# ActuatorMKII_Circuits.net
KiCad netlist of a schematic drawn in Altium Designer
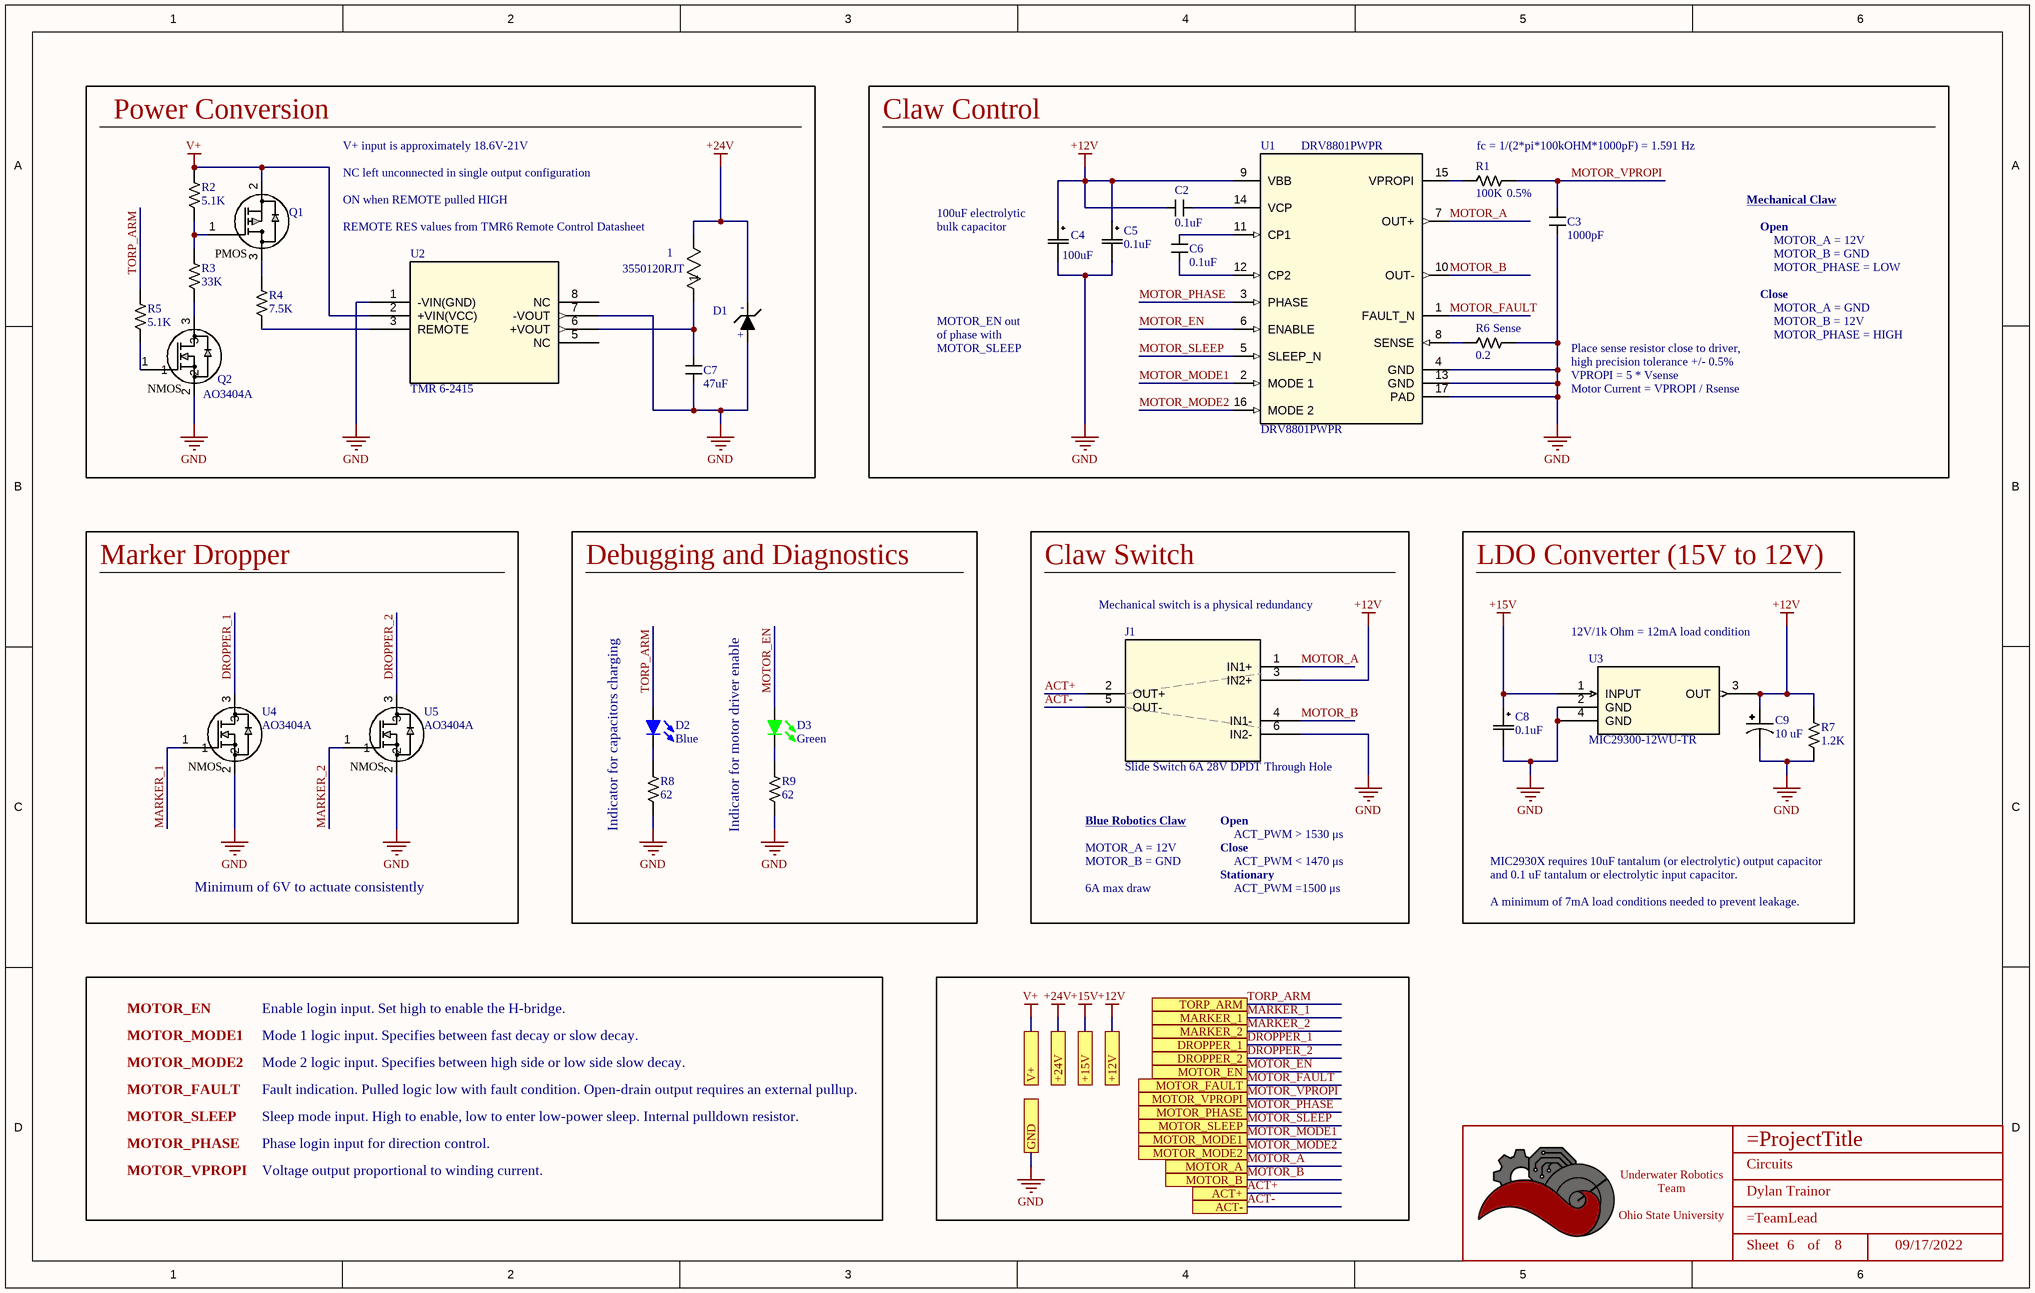
[diagram p0: ActuatorMKII_Circuits.SchDoc]

(export (version "E")
  (design (tool "Eeschema 10.0.6"))
  (components
    (comp (ref "*")
      (value "Title_Block")
      (footprint "LOGO")
      (description "UWRT Schematic Title Block Template\r\n\r\nCreated June 2021, Dylan Trainor")
      (libsource (lib "UWRT") (part "Title_Block"))
    )
    (comp (ref "1")
      (value "3550120RJT")
      (footprint "RES_3550_TEC")
      (description "RES 3550 120R 5%")
      (fields (field (name "COPYRIGHT") "Copyright (C) 2022 Ultra Librarian. All rights reserved."))
      (libsource (lib "Resistors") (part "3550120RJT"))
    )
    (comp (ref "C2")
      (value "0.1uF")
      (footprint "CAPACITOR_0805")
      (description "Cap 100nF 50V +/-10%\r\nCeramic 0805")
      (fields
        (field (name "TOLERANCE") "+/- 10%")
        (field (name "VOLTAGE") "25V")
        (field (name "MADE BY") "Robert Pafford")
      )
      (libsource (lib "Capacitors") (part "CAPACITOR_0.1uF_0402_1"))
    )
    (comp (ref "C3")
      (value "1000pF")
      (footprint "CAPACITOR_0603")
      (description "Cap 1000pF 50V +/-2%\r\nCeramic 0603")
      (fields
        (field (name "TOLERANCE") "+/- 2%")
        (field (name "VOLTAGE") "50")
        (field (name "MADE BY") "Flip B")
      )
      (libsource (lib "Capacitors") (part "CAPACITOR_0.001uF_0603"))
    )
    (comp (ref "C4")
      (value "100uF")
      (footprint "CAPAE830X1100N")
      (description "Aluminum Electrolytic Capacitors - SMD 35V 100uF 0810 20%")
      (fields (field (name "CREATED BY") "John Ulm"))
      (libsource (lib "Capacitors") (part "CAP ALUM 100UF 20% 35V SMD (2)"))
    )
    (comp (ref "C5")
      (value "0.1uF")
      (footprint "U2-D_NCH")
      (description "0.1 µF 35 V Aluminum Electrolytic Capacitors Radial, Can - SMD 7000 Hrs @ 105°C")
      (fields
        (field (name "MANUFACTURER_PART_NUMBER") "UCB1V0R1MCL1GS")
        (field (name "Comment") "0.1uF electrolytic 35 V")
        (field (name "COPYRIGHT") "Copyright (C) 2022 Ultra Librarian. All rights reserved.")
        (field (name "MADE BY") "Tyson Nguyen")
      )
      (libsource (lib "Capacitors") (part "CAP ALUM 0.1UF 20% 35V SMD"))
    )
    (comp (ref "C6")
      (value "0.1uF")
      (footprint "CAPACITOR_0805")
      (description "Cap 100nF 50V +/-10%\r\nCeramic 0805")
      (fields
        (field (name "TOLERANCE") "+/- 10%")
        (field (name "VOLTAGE") "25V")
        (field (name "MADE BY") "Robert Pafford")
      )
      (libsource (lib "Capacitors") (part "CAPACITOR_0.1uF_0402_1"))
    )
    (comp (ref "C7")
      (value "47uF")
      (footprint "PCAP_8x5.4-ELECT_NCA")
      (description "CAP ALUM 47uF 50V +/-20%\r\n8x5.4")
      (fields
        (field (name "TOLERANCE") "+/- 20%")
        (field (name "VOLTAGE") "6.3V")
        (field (name "MADE BY") "Flip B")
      )
      (libsource (lib "Capacitors") (part "CAP_ALUM_47uF"))
    )
    (comp (ref "C8")
      (value "0.1uF")
      (footprint "U2-D_NCH")
      (description "0.1 µF 35 V Aluminum Electrolytic Capacitors Radial, Can - SMD 7000 Hrs @ 105°C")
      (fields
        (field (name "MANUFACTURER_PART_NUMBER") "UCB1V0R1MCL1GS")
        (field (name "Comment") "0.1uF electrolytic 35 V")
        (field (name "COPYRIGHT") "Copyright (C) 2022 Ultra Librarian. All rights reserved.")
        (field (name "MADE BY") "Tyson Nguyen")
      )
      (libsource (lib "Capacitors") (part "CAP ALUM 0.1UF 20% 35V SMD"))
    )
    (comp (ref "C9")
      (value "10uF Tantalum 16V")
      (footprint "CAPACITOR_1206 - POLAR")
      (description "Cap 10uF 16V +/-20%\r\nTantalum 1206")
      (fields
        (field (name "TOLERANCE") "+/- 10%")
        (field (name "VOLTAGE") "16V")
        (field (name "VALUE (UF)") "10 uF")
        (field (name "MADE BY") "Dylan T")
      )
      (libsource (lib "Capacitors") (part "CAPACITOR_10uF_1206_Tantalum_1"))
    )
    (comp (ref "D1")
      (value "Zener_Diode_10V_410mW")
      (footprint "SOD-123")
      (description "Zener Diode ¦ 10 V ¦ 410 mW ¦ SOD 123")
      (fields (field (name "POWER") "410mW") (field (name "MADE BY") "Nathan A"))
      (libsource (lib "Diodes") (part "Zener_Diode_10V_410mW"))
    )
    (comp (ref "D2")
      (value "150060BS75000")
      (footprint "LED_0603")
      (description "LED Blue Vf= 3.2V If = 0.020A\r\n150060BS75000")
      (fields (field (name "COLOR") "Blue") (field (name "MADE BY") "Robert Pafford"))
      (libsource (lib "Diodes") (part "LED_Blue_0603"))
    )
    (comp (ref "D3")
      (value "IN-S63AT5G")
      (footprint "LED_0603")
      (description "LED Green Vf= 3V If = 0.005A\r\nIN-S63AT5G")
      (fields (field (name "COLOR") "Green") (field (name "MADE BY") "Robert Pafford"))
      (libsource (lib "Diodes") (part "LED_Green_0603_3V"))
    )
    (comp (ref "J1")
      (value "Slide Switch 6A 28V DPDT Through Hole")
      (footprint "CONN_S3CQE2")
      (description "SWITCH SLIDE DPDT 6A 28V Through Hole")
      (fields
        (field (name "MANUFACTURER_PART_NUMBER") "1201M2S3CQE2")
        (field (name "COPYRIGHT") "Copyright (C) 2022 Ultra Librarian. All rights reserved.")
      )
      (libsource (lib "Switches") (part "Slide DPDT Switch"))
    )
    (comp (ref "Q1")
      (value "DMP3056L-7")
      (footprint "SOT-23-3")
      (description "P-Channel 30V 4.3A (Ta) 1.38W (Ta) Surface Mount SOT23")
      (fields (field (name "CREATED BY") "John Ulm") (field (name "REVIEWED BY") "---"))
      (libsource (lib "Transistors") (part "DMP3056L-7"))
    )
    (comp (ref "Q2")
      (value "AO3404A")
      (footprint "SOT-23-3")
      (description "N-Channel 30 V 5.8A (Ta) 1.4W (Ta) Surface Mount SOT-23-3")
      (fields (field (name "CREATED BY") "Dylan T"))
      (libsource (lib "Transistors") (part "AO3404A"))
    )
    (comp (ref "R1")
      (value "100k Ohm 5% 1/8W")
      (footprint "RESISTOR_0603")
      (description "RES 100k OHM 5% 1/10W 0603")
      (fields
        (field (name "TOLERANCE") "+/- 5%")
        (field (name "VALUE  (OHMS)") "100K")
        (field (name "MADE BY") "Flip B")
      )
      (libsource (lib "Resistors") (part "RESISTOR_100K_0603_1"))
    )
    (comp (ref "R2")
      (value "5.1k Ohm 1% 1/8W")
      (footprint "RESISTOR_0805")
      (description "RES 5.1k OHM 1% 1/8W 0805")
      (fields
        (field (name "TOLERANCE") "+/- 5%")
        (field (name "VALUE  (OHMS)") "5.1K")
        (field (name "MADE BY") "Dylan Trainor")
      )
      (libsource (lib "Resistors") (part "RESISTOR_5.1K_0805"))
    )
    (comp (ref "R3")
      (value "33k Ohm 5% 1/8W")
      (footprint "RESISTOR_0805")
      (description "RES 33k OHM 5% 1/8W 0805")
      (fields
        (field (name "TOLERANCE") "+/- 5%")
        (field (name "VALUE  (OHMS)") "33K")
        (field (name "MADE BY") "Dylan Trainor")
      )
      (libsource (lib "Resistors") (part "RESISTOR_33K_0805"))
    )
    (comp (ref "R4")
      (value "7.5k Ohm 5% 1/10W")
      (footprint "RESISTOR_0603")
      (description "RES 7.5k OHM 5% 1/10W 0603")
      (fields
        (field (name "TOLERANCE") "+/- 5%")
        (field (name "VALUE  (OHMS)") "7.5K")
        (field (name "MADE BY") "Dylan Trainor")
      )
      (libsource (lib "Resistors") (part "RESISTOR_7.5K_0603"))
    )
    (comp (ref "R5")
      (value "5.1k Ohm 1% 1/8W")
      (footprint "RESISTOR_0805")
      (description "RES 5.1k OHM 1% 1/8W 0805")
      (fields
        (field (name "TOLERANCE") "+/- 5%")
        (field (name "VALUE  (OHMS)") "5.1K")
        (field (name "MADE BY") "Dylan Trainor")
      )
      (libsource (lib "Resistors") (part "RESISTOR_5.1K_0805"))
    )
    (comp (ref "R6")
      (value "0.2 Ohm 1% 2W 2512")
      (footprint "RESISTOR_2512")
      (description "RES 0.2 OHM 1% 2W 2512")
      (fields
        (field (name "TOLERANCE") "+/- 1%")
        (field (name "VALUE  (OHMS)") "0.2")
        (field (name "MADE BY") "Dylan Trainor")
      )
      (libsource (lib "Resistors") (part "RESISTOR_0.2_1%_2512"))
    )
    (comp (ref "R7")
      (value "1.2k Ohm 5% 1/2W")
      (footprint "RESISTOR_0805")
      (description "RES 1.2k OHM 5% 1/2W 0805")
      (fields
        (field (name "TOLERANCE") "+/- 5%")
        (field (name "VALUE  (OHMS)") "1.2K")
        (field (name "MADE BY") "Robert Pafford")
      )
      (libsource (lib "Resistors") (part "RESISTOR_1.2K_0805"))
    )
    (comp (ref "R8")
      (value "62 Ohm 1% 1/4W")
      (footprint "RESISTOR_0603")
      (description "RES SMD 62 OHM 1% 1/4W 0603")
      (fields
        (field (name "TOLERANCE") "+/- 1%")
        (field (name "VALUE  (OHMS)") "62")
        (field (name "MADE BY") "Robert Pafford")
      )
      (libsource (lib "Resistors") (part "RESISTOR_62_0603"))
    )
    (comp (ref "R9")
      (value "62 Ohm 1% 1/4W")
      (footprint "RESISTOR_0603")
      (description "RES SMD 62 OHM 1% 1/4W 0603")
      (fields
        (field (name "TOLERANCE") "+/- 1%")
        (field (name "VALUE  (OHMS)") "62")
        (field (name "MADE BY") "Robert Pafford")
      )
      (libsource (lib "Resistors") (part "RESISTOR_62_0603"))
    )
    (comp (ref "U1")
      (value "DRV8801PWPR")
      (footprint "PWP0016B")
      (description "Bipolar Motor Driver DMOS Parallel 16-HTSSOP")
      (fields
        (field (name "PARTNUMBER") "DRV8801PWP")
        (field (name "MANUFACTURER") "Texas Instruments")
        (field (name "COPYRIGHT") "Copyright (C) 2022 Ultra Librarian. All rights reserved.")
      )
      (libsource (lib "Integrated Circuits") (part "DRV8801PWPR"))
    )
    (comp (ref "U2")
      (value "TMR 6-2415")
      (footprint "TMR 6_TRP")
      (description "No Description Available")
      (fields (field (name "COPYRIGHT") "Copyright (C) 2022 Ultra Librarian. All rights reserved."))
      (libsource (lib "Converter") (part "TMR 6-2415"))
    )
    (comp (ref "U3")
      (value "MIC29300-12WU-TR")
      (footprint "TO-263-3_MCH")
      (description "Linear Voltage Regulator IC Positive Fixed 1 Output 3A TO-263-3")
      (fields (field (name "COPYRIGHT") "Copyright (C) 2022 Ultra Librarian. All rights reserved."))
      (libsource (lib "Converter") (part "MIC29300-12WU-TR"))
    )
    (comp (ref "U4")
      (value "AO3404A")
      (footprint "SOT-23-3")
      (description "N-Channel 30 V 5.8A (Ta) 1.4W (Ta) Surface Mount SOT-23-3")
      (fields (field (name "CREATED BY") "Dylan T"))
      (libsource (lib "Transistors") (part "AO3404A"))
    )
    (comp (ref "U5")
      (value "AO3404A")
      (footprint "SOT-23-3")
      (description "N-Channel 30 V 5.8A (Ta) 1.4W (Ta) Surface Mount SOT-23-3")
      (fields (field (name "CREATED BY") "Dylan T"))
      (libsource (lib "Transistors") (part "AO3404A"))
    )
  )
  (nets
    (net (code "1") (name "+12V") (class "Default")
      (node (ref "C2") (pin "2") (pinfunction "2_2") (pintype "passive"))
      (node (ref "C4") (pin "1") (pinfunction "1_1") (pintype "passive"))
      (node (ref "C5") (pin "1") (pinfunction "1_1") (pintype "passive"))
      (node (ref "C9") (pin "1") (pintype "passive"))
      (node (ref "J1") (pin "3") (pinfunction "IN2+_3") (pintype "passive"))
      (node (ref "R7") (pin "1") (pinfunction "1_1") (pintype "passive"))
      (node (ref "U1") (pin "9") (pinfunction "VBB_9") (pintype "power_in"))
      (node (ref "U3") (pin "3") (pinfunction "OUT_3") (pintype "output"))
    )
    (net (code "2") (name "+15V") (class "Default")
      (node (ref "C8") (pin "1") (pinfunction "1_1") (pintype "passive"))
      (node (ref "U3") (pin "1") (pinfunction "INPUT_1") (pintype "input"))
    )
    (net (code "3") (name "+24V") (class "Default")
      (node (ref "1") (pin "2") (pinfunction "2_2") (pintype "passive"))
      (node (ref "D1") (pin "2") (pinfunction "2_2") (pintype "passive"))
    )
    (net (code "4") (name "/ACT+") (class "Default")
      (node (ref "J1") (pin "2") (pinfunction "OUT+_2") (pintype "passive"))
    )
    (net (code "5") (name "/ACT-") (class "Default")
      (node (ref "J1") (pin "5") (pinfunction "OUT-_5") (pintype "passive"))
    )
    (net (code "6") (name "/DROPPER_1") (class "Default")
      (node (ref "U4") (pin "3") (pinfunction "3_3") (pintype "passive"))
    )
    (net (code "7") (name "/DROPPER_2") (class "Default")
      (node (ref "U5") (pin "3") (pinfunction "3_3") (pintype "passive"))
    )
    (net (code "8") (name "/MARKER_1") (class "Default")
      (node (ref "U4") (pin "1") (pinfunction "1_1") (pintype "passive"))
    )
    (net (code "9") (name "/MARKER_2") (class "Default")
      (node (ref "U5") (pin "1") (pinfunction "1_1") (pintype "passive"))
    )
    (net (code "10") (name "/MOTOR_A") (class "Default")
      (node (ref "J1") (pin "1") (pinfunction "IN1+_1") (pintype "passive"))
      (node (ref "U1") (pin "7") (pinfunction "OUT+_7") (pintype "output"))
    )
    (net (code "11") (name "/MOTOR_B") (class "Default")
      (node (ref "J1") (pin "4") (pinfunction "IN1-_4") (pintype "passive"))
      (node (ref "U1") (pin "10") (pinfunction "OUT-_10") (pintype "output"))
    )
    (net (code "12") (name "/MOTOR_EN") (class "Default")
      (node (ref "D3") (pin "1") (pinfunction "1_1") (pintype "passive"))
      (node (ref "U1") (pin "6") (pinfunction "ENABLE_6") (pintype "input"))
    )
    (net (code "13") (name "/MOTOR_FAULT") (class "Default")
      (node (ref "U1") (pin "1") (pinfunction "FAULT_N_1") (pintype "open_collector"))
    )
    (net (code "14") (name "/MOTOR_MODE1") (class "Default")
      (node (ref "U1") (pin "2") (pinfunction "MODE_1_2") (pintype "input"))
    )
    (net (code "15") (name "/MOTOR_MODE2") (class "Default")
      (node (ref "U1") (pin "16") (pinfunction "MODE_2_16") (pintype "input"))
    )
    (net (code "16") (name "/MOTOR_PHASE") (class "Default")
      (node (ref "U1") (pin "3") (pinfunction "PHASE_3") (pintype "input"))
    )
    (net (code "17") (name "/MOTOR_SLEEP") (class "Default")
      (node (ref "U1") (pin "5") (pinfunction "SLEEP_N_5") (pintype "input"))
    )
    (net (code "18") (name "/MOTOR_VPROPI") (class "Default")
      (node (ref "C3") (pin "1") (pinfunction "1_1") (pintype "passive"))
      (node (ref "R1") (pin "1") (pinfunction "1_1") (pintype "passive"))
    )
    (net (code "19") (name "/TORP_ARM") (class "Default")
      (node (ref "D2") (pin "1") (pinfunction "1_1") (pintype "passive"))
      (node (ref "R5") (pin "1") (pinfunction "1_1") (pintype "passive"))
    )
    (net (code "20") (name "GND") (class "Default")
      (node (ref "C3") (pin "2") (pinfunction "2_2") (pintype "passive"))
      (node (ref "C4") (pin "2") (pinfunction "2_2") (pintype "passive"))
      (node (ref "C5") (pin "2") (pinfunction "2_2") (pintype "passive"))
      (node (ref "C7") (pin "2") (pinfunction "2_2") (pintype "passive"))
      (node (ref "C8") (pin "2") (pinfunction "2_2") (pintype "passive"))
      (node (ref "C9") (pin "2") (pintype "passive"))
      (node (ref "D1") (pin "1") (pinfunction "1_1") (pintype "passive"))
      (node (ref "J1") (pin "6") (pinfunction "IN2-_6") (pintype "passive"))
      (node (ref "Q2") (pin "2") (pinfunction "2_2") (pintype "passive"))
      (node (ref "R6") (pin "1") (pinfunction "1_1") (pintype "passive"))
      (node (ref "R7") (pin "2") (pinfunction "2_2") (pintype "passive"))
      (node (ref "R8") (pin "2") (pinfunction "2_2") (pintype "passive"))
      (node (ref "R9") (pin "2") (pinfunction "2_2") (pintype "passive"))
      (node (ref "U1") (pin "13") (pinfunction "GND_13") (pintype "power_in"))
      (node (ref "U1") (pin "17") (pinfunction "PAD_17") (pintype "power_in"))
      (node (ref "U1") (pin "4") (pinfunction "GND_4") (pintype "power_in"))
      (node (ref "U2") (pin "1") (pinfunction "-VIN(GND)_1") (pintype "power_in"))
      (node (ref "U2") (pin "7") (pinfunction "-VOUT_7") (pintype "output"))
      (node (ref "U3") (pin "2") (pinfunction "GND_2") (pintype "power_in"))
      (node (ref "U3") (pin "4") (pinfunction "GND_4") (pintype "power_in"))
      (node (ref "U4") (pin "2") (pinfunction "2_2") (pintype "passive"))
      (node (ref "U5") (pin "2") (pinfunction "2_2") (pintype "passive"))
    )
    (net (code "21") (name "Net-(D2-Pad2)") (class "Default")
      (node (ref "D2") (pin "2") (pinfunction "2_2") (pintype "passive"))
      (node (ref "R8") (pin "1") (pinfunction "1_1") (pintype "passive"))
    )
    (net (code "22") (name "Net-(D3-Pad2)") (class "Default")
      (node (ref "D3") (pin "2") (pinfunction "2_2") (pintype "passive"))
      (node (ref "R9") (pin "1") (pinfunction "1_1") (pintype "passive"))
    )
    (net (code "23") (name "Net-(Q1-Pad1)") (class "Default")
      (node (ref "Q1") (pin "1") (pinfunction "1_1") (pintype "passive"))
      (node (ref "R2") (pin "2") (pinfunction "2_2") (pintype "passive"))
      (node (ref "R3") (pin "1") (pinfunction "1_1") (pintype "passive"))
    )
    (net (code "24") (name "Net-(Q1-Pad3)") (class "Default")
      (node (ref "Q1") (pin "3") (pinfunction "3_3") (pintype "passive"))
      (node (ref "R4") (pin "1") (pinfunction "1_1") (pintype "passive"))
    )
    (net (code "25") (name "Net-(Q2-Pad1)") (class "Default")
      (node (ref "Q2") (pin "1") (pinfunction "1_1") (pintype "passive"))
      (node (ref "R5") (pin "2") (pinfunction "2_2") (pintype "passive"))
    )
    (net (code "26") (name "Net-(Q2-Pad3)") (class "Default")
      (node (ref "Q2") (pin "3") (pinfunction "3_3") (pintype "passive"))
      (node (ref "R3") (pin "2") (pinfunction "2_2") (pintype "passive"))
    )
    (net (code "27") (name "Net-(U1-CP1)") (class "Default")
      (node (ref "C6") (pin "1") (pinfunction "1_1") (pintype "passive"))
      (node (ref "U1") (pin "11") (pinfunction "CP1_11") (pintype "input"))
    )
    (net (code "28") (name "Net-(U1-CP2)") (class "Default")
      (node (ref "C6") (pin "2") (pinfunction "2_2") (pintype "passive"))
      (node (ref "U1") (pin "12") (pinfunction "CP2_12") (pintype "input"))
    )
    (net (code "29") (name "Net-(U1-SENSE)") (class "Default")
      (node (ref "R6") (pin "2") (pinfunction "2_2") (pintype "passive"))
      (node (ref "U1") (pin "8") (pinfunction "SENSE_8") (pintype "input"))
    )
    (net (code "30") (name "Net-(U1-VCP)") (class "Default")
      (node (ref "C2") (pin "1") (pinfunction "1_1") (pintype "passive"))
      (node (ref "U1") (pin "14") (pinfunction "VCP_14") (pintype "passive"))
    )
    (net (code "31") (name "Net-(U1-VPROPI)") (class "Default")
      (node (ref "R1") (pin "2") (pinfunction "2_2") (pintype "passive"))
      (node (ref "U1") (pin "15") (pinfunction "VPROPI_15") (pintype "power_in"))
    )
    (net (code "32") (name "Net-(U2-+VOUT)") (class "Default")
      (node (ref "1") (pin "1") (pinfunction "1_1") (pintype "passive"))
      (node (ref "C7") (pin "1") (pinfunction "1_1") (pintype "passive"))
      (node (ref "U2") (pin "6") (pinfunction "+VOUT_6") (pintype "output"))
    )
    (net (code "33") (name "Net-(U2-REMOTE)") (class "Default")
      (node (ref "R4") (pin "2") (pinfunction "2_2") (pintype "passive"))
      (node (ref "U2") (pin "3") (pinfunction "REMOTE_3") (pintype "passive"))
    )
    (net (code "34") (name "V+") (class "Default")
      (node (ref "Q1") (pin "2") (pinfunction "2_2") (pintype "passive"))
      (node (ref "R2") (pin "1") (pinfunction "1_1") (pintype "passive"))
      (node (ref "U2") (pin "2") (pinfunction "+VIN(VCC)_2") (pintype "power_in"))
    )
    (net (code "35") (name "unconnected-(U2-NC-Pad5)") (class "Default")
      (node (ref "U2") (pin "5") (pinfunction "NC_5") (pintype "passive"))
    )
    (net (code "36") (name "unconnected-(U2-NC-Pad8)") (class "Default")
      (node (ref "U2") (pin "8") (pinfunction "NC_8") (pintype "passive"))
    )
  )
)
